# fpga.net
KiCad netlist of a schematic drawn in Altium Designer
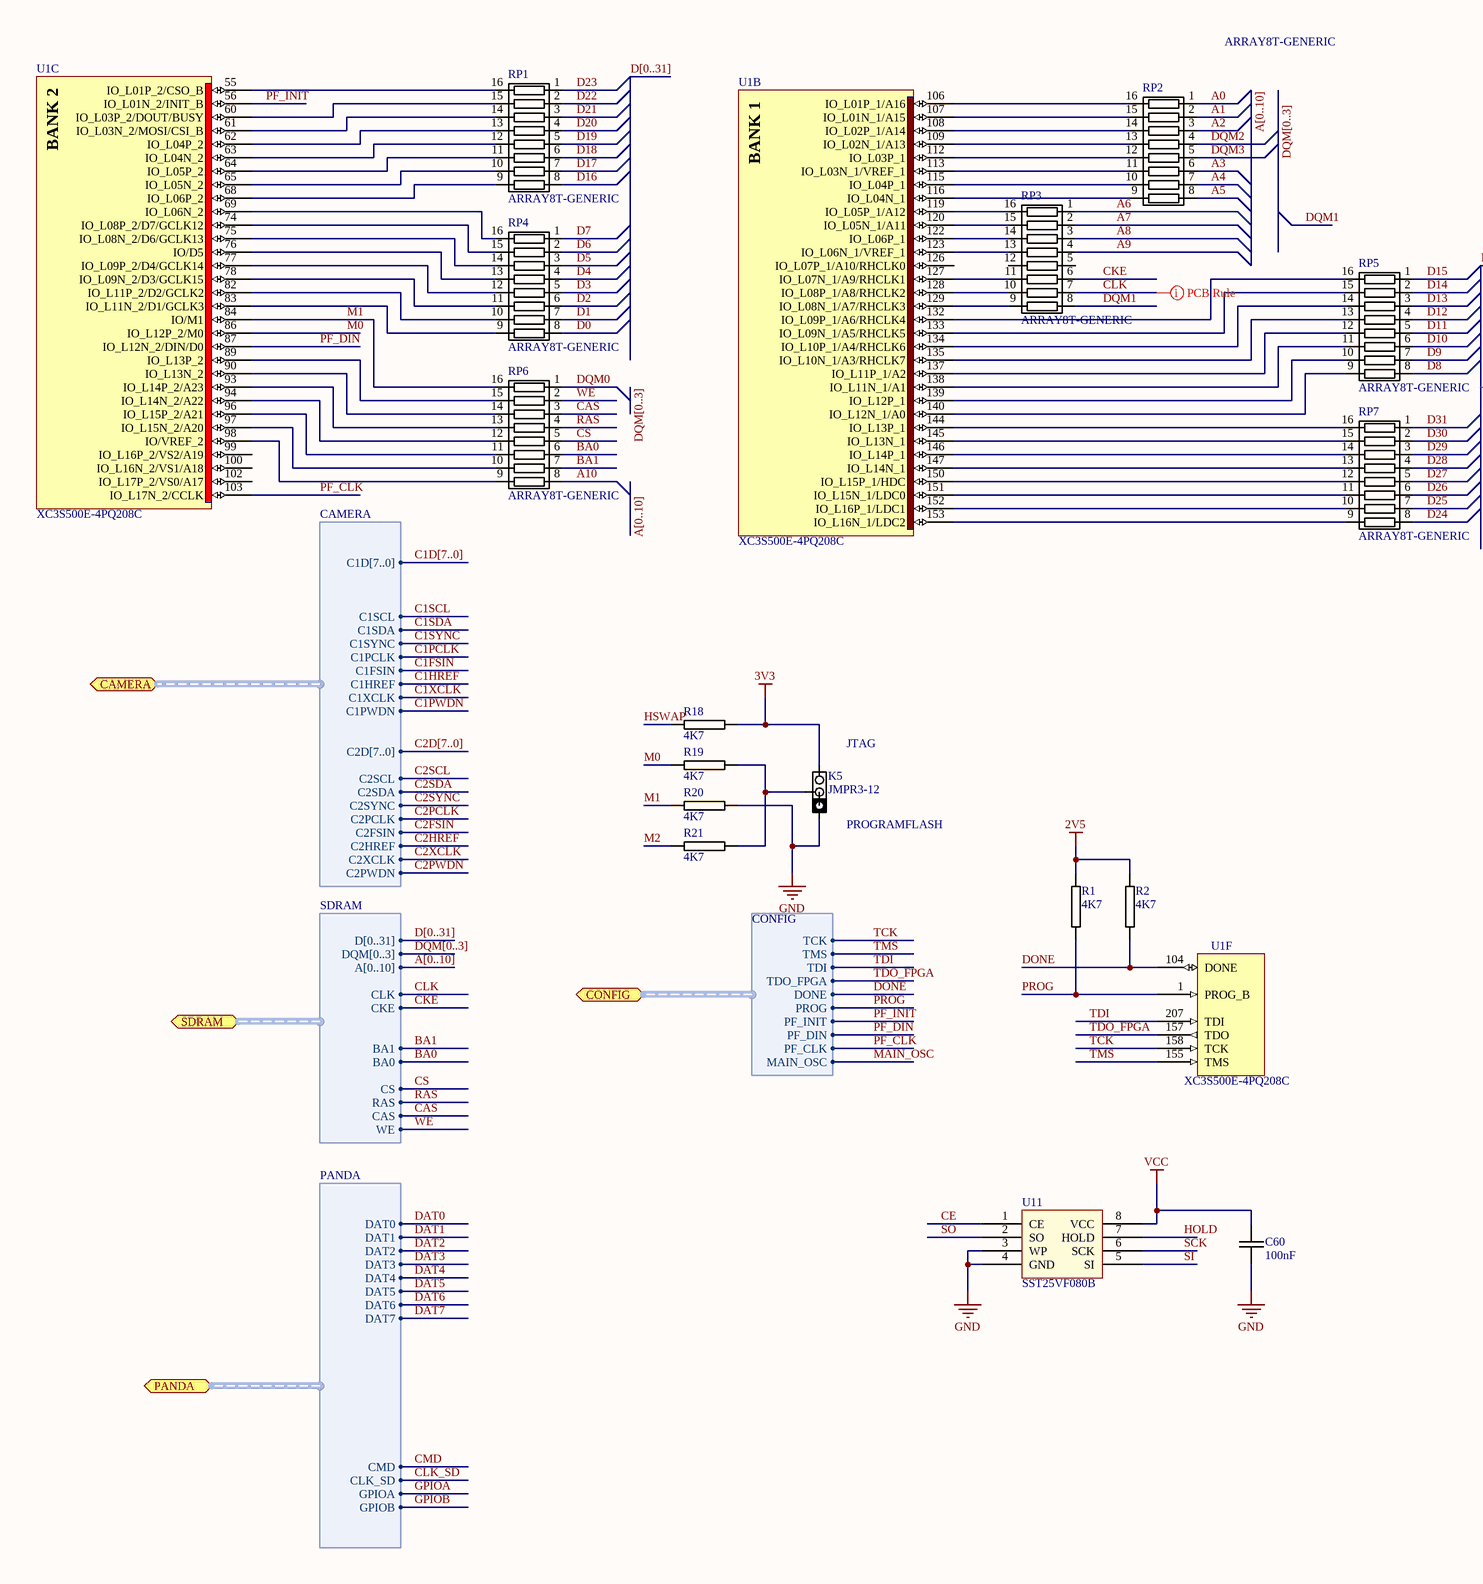
[diagram p0: fpga.SchDoc, left]
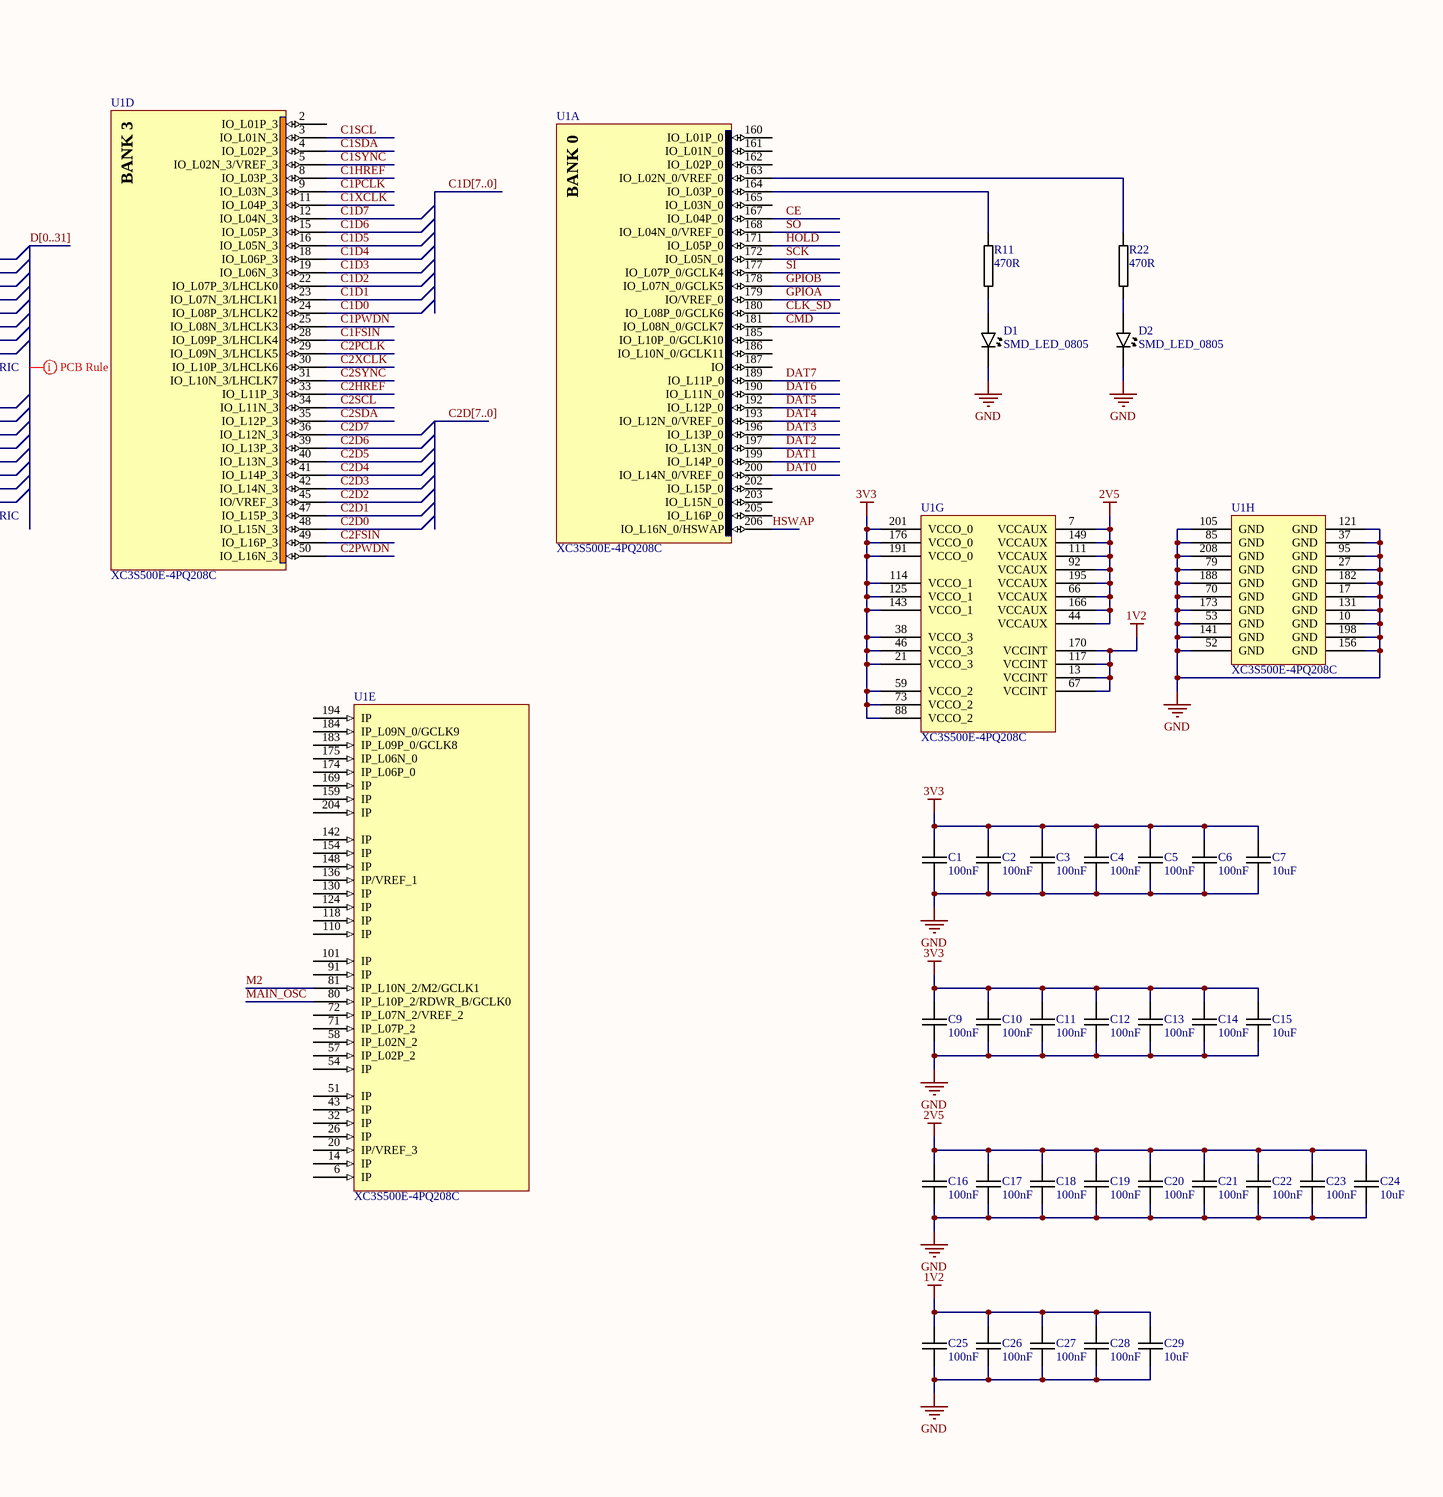
[diagram p1: fpga.SchDoc, right]

(export (version "E")
  (design (tool "Eeschema 10.0.6"))
  (components
    (comp (ref "C1")
      (value "100nF")
      (footprint "0603C-GENERIC")
      (description "GENERIC CAPACITOR NON POLARISED 0603")
      (fields (field (name "TOLERANCE") "±10%") (field (name "MANUFACTURER PART NUMBER") "C1608X7R1H103K"))
      (libsource (lib "vh_Altium Library") (part "0603C-100NF-50V-X7R-TDK"))
    )
    (comp (ref "C2")
      (value "100nF")
      (footprint "0603C-GENERIC")
      (description "GENERIC CAPACITOR NON POLARISED 0603")
      (fields (field (name "TOLERANCE") "±10%") (field (name "MANUFACTURER PART NUMBER") "C1608X7R1H103K"))
      (libsource (lib "vh_Altium Library") (part "0603C-100NF-50V-X7R-TDK"))
    )
    (comp (ref "C3")
      (value "100nF")
      (footprint "0603C-GENERIC")
      (description "GENERIC CAPACITOR NON POLARISED 0603")
      (fields (field (name "TOLERANCE") "±10%") (field (name "MANUFACTURER PART NUMBER") "C1608X7R1H103K"))
      (libsource (lib "vh_Altium Library") (part "0603C-100NF-50V-X7R-TDK"))
    )
    (comp (ref "C4")
      (value "100nF")
      (footprint "0603C-GENERIC")
      (description "GENERIC CAPACITOR NON POLARISED 0603")
      (fields (field (name "TOLERANCE") "±10%") (field (name "MANUFACTURER PART NUMBER") "C1608X7R1H103K"))
      (libsource (lib "vh_Altium Library") (part "0603C-100NF-50V-X7R-TDK"))
    )
    (comp (ref "C5")
      (value "100nF")
      (footprint "0603C-GENERIC")
      (description "GENERIC CAPACITOR NON POLARISED 0603")
      (fields (field (name "TOLERANCE") "±10%") (field (name "MANUFACTURER PART NUMBER") "C1608X7R1H103K"))
      (libsource (lib "vh_Altium Library") (part "0603C-100NF-50V-X7R-TDK"))
    )
    (comp (ref "C6")
      (value "100nF")
      (footprint "0603C-GENERIC")
      (description "GENERIC CAPACITOR NON POLARISED 0603")
      (fields (field (name "TOLERANCE") "±10%") (field (name "MANUFACTURER PART NUMBER") "C1608X7R1H103K"))
      (libsource (lib "vh_Altium Library") (part "0603C-100NF-50V-X7R-TDK"))
    )
    (comp (ref "C7")
      (value "10uF")
      (footprint "0805C-GENERIC")
      (description "CAPACITOR 0805 CERAMIC")
      (fields
        (field (name "MANUFACTURER PART NUMBER") "C2012X5R1C106M")
        (field (name "MANUFACTURER") "TDK Corporation")
      )
      (libsource (lib "vh_Altium Library") (part "0805C-10UF-16V-X5R-TDK"))
    )
    (comp (ref "C9")
      (value "100nF")
      (footprint "0603C-GENERIC")
      (description "GENERIC CAPACITOR NON POLARISED 0603")
      (fields (field (name "TOLERANCE") "±10%") (field (name "MANUFACTURER PART NUMBER") "C1608X7R1H103K"))
      (libsource (lib "vh_Altium Library") (part "0603C-100NF-50V-X7R-TDK"))
    )
    (comp (ref "C10")
      (value "100nF")
      (footprint "0603C-GENERIC")
      (description "GENERIC CAPACITOR NON POLARISED 0603")
      (fields (field (name "TOLERANCE") "±10%") (field (name "MANUFACTURER PART NUMBER") "C1608X7R1H103K"))
      (libsource (lib "vh_Altium Library") (part "0603C-100NF-50V-X7R-TDK"))
    )
    (comp (ref "C11")
      (value "100nF")
      (footprint "0603C-GENERIC")
      (description "GENERIC CAPACITOR NON POLARISED 0603")
      (fields (field (name "TOLERANCE") "±10%") (field (name "MANUFACTURER PART NUMBER") "C1608X7R1H103K"))
      (libsource (lib "vh_Altium Library") (part "0603C-100NF-50V-X7R-TDK"))
    )
    (comp (ref "C12")
      (value "100nF")
      (footprint "0603C-GENERIC")
      (description "GENERIC CAPACITOR NON POLARISED 0603")
      (fields (field (name "TOLERANCE") "±10%") (field (name "MANUFACTURER PART NUMBER") "C1608X7R1H103K"))
      (libsource (lib "vh_Altium Library") (part "0603C-100NF-50V-X7R-TDK"))
    )
    (comp (ref "C13")
      (value "100nF")
      (footprint "0603C-GENERIC")
      (description "GENERIC CAPACITOR NON POLARISED 0603")
      (fields (field (name "TOLERANCE") "±10%") (field (name "MANUFACTURER PART NUMBER") "C1608X7R1H103K"))
      (libsource (lib "vh_Altium Library") (part "0603C-100NF-50V-X7R-TDK"))
    )
    (comp (ref "C14")
      (value "100nF")
      (footprint "0603C-GENERIC")
      (description "GENERIC CAPACITOR NON POLARISED 0603")
      (fields (field (name "TOLERANCE") "±10%") (field (name "MANUFACTURER PART NUMBER") "C1608X7R1H103K"))
      (libsource (lib "vh_Altium Library") (part "0603C-100NF-50V-X7R-TDK"))
    )
    (comp (ref "C15")
      (value "10uF")
      (footprint "0805C-GENERIC")
      (description "CAPACITOR 0805 CERAMIC")
      (fields
        (field (name "MANUFACTURER PART NUMBER") "C2012X5R1C106M")
        (field (name "MANUFACTURER") "TDK Corporation")
      )
      (libsource (lib "vh_Altium Library") (part "0805C-10UF-16V-X5R-TDK"))
    )
    (comp (ref "C16")
      (value "100nF")
      (footprint "0603C-GENERIC")
      (description "GENERIC CAPACITOR NON POLARISED 0603")
      (fields (field (name "TOLERANCE") "±10%") (field (name "MANUFACTURER PART NUMBER") "C1608X7R1H103K"))
      (libsource (lib "vh_Altium Library") (part "0603C-100NF-50V-X7R-TDK"))
    )
    (comp (ref "C17")
      (value "100nF")
      (footprint "0603C-GENERIC")
      (description "GENERIC CAPACITOR NON POLARISED 0603")
      (fields (field (name "TOLERANCE") "±10%") (field (name "MANUFACTURER PART NUMBER") "C1608X7R1H103K"))
      (libsource (lib "vh_Altium Library") (part "0603C-100NF-50V-X7R-TDK"))
    )
    (comp (ref "C18")
      (value "100nF")
      (footprint "0603C-GENERIC")
      (description "GENERIC CAPACITOR NON POLARISED 0603")
      (fields (field (name "TOLERANCE") "±10%") (field (name "MANUFACTURER PART NUMBER") "C1608X7R1H103K"))
      (libsource (lib "vh_Altium Library") (part "0603C-100NF-50V-X7R-TDK"))
    )
    (comp (ref "C19")
      (value "100nF")
      (footprint "0603C-GENERIC")
      (description "GENERIC CAPACITOR NON POLARISED 0603")
      (fields (field (name "TOLERANCE") "±10%") (field (name "MANUFACTURER PART NUMBER") "C1608X7R1H103K"))
      (libsource (lib "vh_Altium Library") (part "0603C-100NF-50V-X7R-TDK"))
    )
    (comp (ref "C20")
      (value "100nF")
      (footprint "0603C-GENERIC")
      (description "GENERIC CAPACITOR NON POLARISED 0603")
      (fields (field (name "TOLERANCE") "±10%") (field (name "MANUFACTURER PART NUMBER") "C1608X7R1H103K"))
      (libsource (lib "vh_Altium Library") (part "0603C-100NF-50V-X7R-TDK"))
    )
    (comp (ref "C21")
      (value "100nF")
      (footprint "0603C-GENERIC")
      (description "GENERIC CAPACITOR NON POLARISED 0603")
      (fields (field (name "TOLERANCE") "±10%") (field (name "MANUFACTURER PART NUMBER") "C1608X7R1H103K"))
      (libsource (lib "vh_Altium Library") (part "0603C-100NF-50V-X7R-TDK"))
    )
    (comp (ref "C22")
      (value "100nF")
      (footprint "0603C-GENERIC")
      (description "GENERIC CAPACITOR NON POLARISED 0603")
      (fields (field (name "TOLERANCE") "±10%") (field (name "MANUFACTURER PART NUMBER") "C1608X7R1H103K"))
      (libsource (lib "vh_Altium Library") (part "0603C-100NF-50V-X7R-TDK"))
    )
    (comp (ref "C23")
      (value "100nF")
      (footprint "0603C-GENERIC")
      (description "GENERIC CAPACITOR NON POLARISED 0603")
      (fields (field (name "TOLERANCE") "±10%") (field (name "MANUFACTURER PART NUMBER") "C1608X7R1H103K"))
      (libsource (lib "vh_Altium Library") (part "0603C-100NF-50V-X7R-TDK"))
    )
    (comp (ref "C24")
      (value "10uF")
      (footprint "0805C-GENERIC")
      (description "CAPACITOR 0805 CERAMIC")
      (fields
        (field (name "MANUFACTURER PART NUMBER") "C2012X5R1C106M")
        (field (name "MANUFACTURER") "TDK Corporation")
      )
      (libsource (lib "vh_Altium Library") (part "0805C-10UF-16V-X5R-TDK"))
    )
    (comp (ref "C25")
      (value "100nF")
      (footprint "0603C-GENERIC")
      (description "GENERIC CAPACITOR NON POLARISED 0603")
      (fields (field (name "TOLERANCE") "±10%") (field (name "MANUFACTURER PART NUMBER") "C1608X7R1H103K"))
      (libsource (lib "vh_Altium Library") (part "0603C-100NF-50V-X7R-TDK"))
    )
    (comp (ref "C26")
      (value "100nF")
      (footprint "0603C-GENERIC")
      (description "GENERIC CAPACITOR NON POLARISED 0603")
      (fields (field (name "TOLERANCE") "±10%") (field (name "MANUFACTURER PART NUMBER") "C1608X7R1H103K"))
      (libsource (lib "vh_Altium Library") (part "0603C-100NF-50V-X7R-TDK"))
    )
    (comp (ref "C27")
      (value "100nF")
      (footprint "0603C-GENERIC")
      (description "GENERIC CAPACITOR NON POLARISED 0603")
      (fields (field (name "TOLERANCE") "±10%") (field (name "MANUFACTURER PART NUMBER") "C1608X7R1H103K"))
      (libsource (lib "vh_Altium Library") (part "0603C-100NF-50V-X7R-TDK"))
    )
    (comp (ref "C28")
      (value "100nF")
      (footprint "0603C-GENERIC")
      (description "GENERIC CAPACITOR NON POLARISED 0603")
      (fields (field (name "TOLERANCE") "±10%") (field (name "MANUFACTURER PART NUMBER") "C1608X7R1H103K"))
      (libsource (lib "vh_Altium Library") (part "0603C-100NF-50V-X7R-TDK"))
    )
    (comp (ref "C29")
      (value "10uF")
      (footprint "0805C-GENERIC")
      (description "CAPACITOR 0805 CERAMIC")
      (fields
        (field (name "MANUFACTURER PART NUMBER") "C2012X5R1C106M")
        (field (name "MANUFACTURER") "TDK Corporation")
      )
      (libsource (lib "vh_Altium Library") (part "0805C-10UF-16V-X5R-TDK"))
    )
    (comp (ref "C60")
      (value "100nF")
      (footprint "0603C-GENERIC")
      (description "GENERIC CAPACITOR NON POLARISED 0603")
      (fields (field (name "TOLERANCE") "±10%") (field (name "MANUFACTURER PART NUMBER") "C1608X7R1H103K"))
      (libsource (lib "vh_Altium Library") (part "0603C-100NF-50V-X7R-TDK"))
    )
    (comp (ref "D1")
      (value "SMD_LED_0805")
      (footprint "CD2012-0805")
      (libsource (lib "camera_board") (part "SMD_LED_0805"))
    )
    (comp (ref "D2")
      (value "SMD_LED_0805")
      (footprint "CD2012-0805")
      (libsource (lib "camera_board") (part "SMD_LED_0805"))
    )
    (comp (ref "K5")
      (value "JMPR3-12")
      (footprint "JMPR3-CLOSED-12")
      (description "CONN HEADER .100 SINGL STR 36POS")
      (fields (field (name "MANUFACTURER") "Sullins Connector Solutions"))
      (libsource (lib "vh_Altium Library") (part "JMPR3-12"))
    )
    (comp (ref "R1")
      (value "4K7")
      (footprint "0603R-4K7")
      (description "GENERIC RESISTOR 0603")
      (fields
        (field (name "MANUFACTURER") "Stackpole Electronics Inc")
        (field (name "MANUFACTURER PART NUMBER") "RMCF 1/16 4.7K 1% R")
      )
      (libsource (lib "vh_Altium Library") (part "0603R-4K7"))
    )
    (comp (ref "R2")
      (value "4K7")
      (footprint "0603R-4K7")
      (description "GENERIC RESISTOR 0603")
      (fields
        (field (name "MANUFACTURER") "Stackpole Electronics Inc")
        (field (name "MANUFACTURER PART NUMBER") "RMCF 1/16 4.7K 1% R")
      )
      (libsource (lib "vh_Altium Library") (part "0603R-4K7"))
    )
    (comp (ref "R11")
      (value "470R")
      (footprint "0603R-470")
      (description "GENERIC RESISTOR 0603")
      (fields (field (name "MANUFACTURER PART NUMBER") "RMCF 1/16 470 1% R") (field (name "TOLERANCE") "±1%"))
      (libsource (lib "vh_Altium Library") (part "0603R-470"))
    )
    (comp (ref "R18")
      (value "4K7")
      (footprint "0603R-4K7")
      (description "GENERIC RESISTOR 0603")
      (fields
        (field (name "MANUFACTURER") "Stackpole Electronics Inc")
        (field (name "MANUFACTURER PART NUMBER") "RMCF 1/16 4.7K 1% R")
      )
      (libsource (lib "vh_Altium Library") (part "0603R-4K7"))
    )
    (comp (ref "R19")
      (value "4K7")
      (footprint "0603R-4K7")
      (description "GENERIC RESISTOR 0603")
      (fields
        (field (name "MANUFACTURER") "Stackpole Electronics Inc")
        (field (name "MANUFACTURER PART NUMBER") "RMCF 1/16 4.7K 1% R")
      )
      (libsource (lib "vh_Altium Library") (part "0603R-4K7"))
    )
    (comp (ref "R20")
      (value "4K7")
      (footprint "0603R-4K7")
      (description "GENERIC RESISTOR 0603")
      (fields
        (field (name "MANUFACTURER") "Stackpole Electronics Inc")
        (field (name "MANUFACTURER PART NUMBER") "RMCF 1/16 4.7K 1% R")
      )
      (libsource (lib "vh_Altium Library") (part "0603R-4K7"))
    )
    (comp (ref "R21")
      (value "4K7")
      (footprint "0603R-4K7")
      (description "GENERIC RESISTOR 0603")
      (fields
        (field (name "MANUFACTURER") "Stackpole Electronics Inc")
        (field (name "MANUFACTURER PART NUMBER") "RMCF 1/16 4.7K 1% R")
      )
      (libsource (lib "vh_Altium Library") (part "0603R-4K7"))
    )
    (comp (ref "R22")
      (value "470R")
      (footprint "0603R-470")
      (description "GENERIC RESISTOR 0603")
      (fields (field (name "MANUFACTURER PART NUMBER") "RMCF 1/16 470 1% R") (field (name "TOLERANCE") "±1%"))
      (libsource (lib "vh_Altium Library") (part "0603R-470"))
    )
    (comp (ref "RP1")
      (value "ARRAY8T-GENERIC")
      (footprint "1206-ARRAY-8-GENERIC")
      (description "GENERIC RESISTOR ARRAY 8X INDEPENDENT")
      (libsource (lib "vh_Altium Library") (part "ARRAY8T-GENERIC"))
    )
    (comp (ref "RP2")
      (value "ARRAY8T-GENERIC")
      (footprint "1206-ARRAY-8-GENERIC")
      (description "GENERIC RESISTOR ARRAY 8X INDEPENDENT")
      (libsource (lib "vh_Altium Library") (part "ARRAY8T-GENERIC"))
    )
    (comp (ref "RP3")
      (value "ARRAY8T-GENERIC")
      (footprint "1206-ARRAY-8-GENERIC")
      (description "GENERIC RESISTOR ARRAY 8X INDEPENDENT")
      (libsource (lib "vh_Altium Library") (part "ARRAY8T-GENERIC"))
    )
    (comp (ref "RP4")
      (value "ARRAY8T-GENERIC")
      (footprint "1206-ARRAY-8-GENERIC")
      (description "GENERIC RESISTOR ARRAY 8X INDEPENDENT")
      (libsource (lib "vh_Altium Library") (part "ARRAY8T-GENERIC"))
    )
    (comp (ref "RP5")
      (value "ARRAY8T-GENERIC")
      (footprint "1206-ARRAY-8-GENERIC")
      (description "GENERIC RESISTOR ARRAY 8X INDEPENDENT")
      (libsource (lib "vh_Altium Library") (part "ARRAY8T-GENERIC"))
    )
    (comp (ref "RP6")
      (value "ARRAY8T-GENERIC")
      (footprint "1206-ARRAY-8-GENERIC")
      (description "GENERIC RESISTOR ARRAY 8X INDEPENDENT")
      (libsource (lib "vh_Altium Library") (part "ARRAY8T-GENERIC"))
    )
    (comp (ref "RP7")
      (value "ARRAY8T-GENERIC")
      (footprint "1206-ARRAY-8-GENERIC")
      (description "GENERIC RESISTOR ARRAY 8X INDEPENDENT")
      (libsource (lib "vh_Altium Library") (part "ARRAY8T-GENERIC"))
    )
    (comp (ref "U1")
      (value "XC3S500E-4PQ208C")
      (footprint "PQ208_N")
      (description "Spartan-3E 1.2V FPGA, 158 User I/Os, 208-Pin PQFP, Standard Performance, Commercial Grade")
      (fields (field (name "PUBLISHER") "Altium Limited"))
      (libsource (lib "Xilinx Spartan-3E") (part "XC3S500E-4PQ208C"))
    )
    (comp (ref "U11")
      (value "SST25VF080B")
      (footprint "SOIC127P600-8BM")
      (libsource (lib "camera_board") (part "SST25VF080B"))
    )
  )
  (nets
    (net (code "5") (name "/A0") (class "Default") (node (ref "RP2") (pin "1") (pintype "passive")))
    (net (code "6") (name "/A1") (class "Default") (node (ref "RP2") (pin "2") (pintype "passive")))
    (net (code "7") (name "/A2") (class "Default") (node (ref "RP2") (pin "3") (pintype "passive")))
    (net (code "8") (name "/A3") (class "Default") (node (ref "RP2") (pin "6") (pintype "passive")))
    (net (code "9") (name "/A4") (class "Default") (node (ref "RP2") (pin "7") (pintype "passive")))
    (net (code "10") (name "/A5") (class "Default") (node (ref "RP2") (pin "8") (pintype "passive")))
    (net (code "11") (name "/A6") (class "Default") (node (ref "RP3") (pin "1") (pintype "passive")))
    (net (code "12") (name "/A7") (class "Default") (node (ref "RP3") (pin "2") (pintype "passive")))
    (net (code "13") (name "/A8") (class "Default") (node (ref "RP3") (pin "3") (pintype "passive")))
    (net (code "14") (name "/A9") (class "Default") (node (ref "RP3") (pin "4") (pintype "passive")))
    (net (code "15") (name "/A10") (class "Default") (node (ref "RP6") (pin "8") (pintype "passive")))
    (net (code "17") (name "/BA0") (class "Default") (node (ref "RP6") (pin "6") (pintype "passive")))
    (net (code "18") (name "/BA1") (class "Default") (node (ref "RP6") (pin "7") (pintype "passive")))
    (net (code "19") (name "/C1D0") (class "Default")
      (node (ref "U1") (pin "24") (pinfunction "IO_L08P_3/LHCLK2_24") (pintype "bidirectional"))
    )
    (net (code "20") (name "/C1D1") (class "Default")
      (node (ref "U1") (pin "23") (pinfunction "IO_L07N_3/LHCLK1_23") (pintype "bidirectional"))
    )
    (net (code "21") (name "/C1D2") (class "Default")
      (node (ref "U1") (pin "22") (pinfunction "IO_L07P_3/LHCLK0_22") (pintype "bidirectional"))
    )
    (net (code "22") (name "/C1D3") (class "Default")
      (node (ref "U1") (pin "19") (pinfunction "IO_L06N_3_19") (pintype "bidirectional"))
    )
    (net (code "23") (name "/C1D4") (class "Default")
      (node (ref "U1") (pin "18") (pinfunction "IO_L06P_3_18") (pintype "bidirectional"))
    )
    (net (code "24") (name "/C1D5") (class "Default")
      (node (ref "U1") (pin "16") (pinfunction "IO_L05N_3_16") (pintype "bidirectional"))
    )
    (net (code "25") (name "/C1D6") (class "Default")
      (node (ref "U1") (pin "15") (pinfunction "IO_L05P_3_15") (pintype "bidirectional"))
    )
    (net (code "26") (name "/C1D7") (class "Default")
      (node (ref "U1") (pin "12") (pinfunction "IO_L04N_3_12") (pintype "bidirectional"))
    )
    (net (code "28") (name "/C1FSIN") (class "Default")
      (node (ref "U1") (pin "28") (pinfunction "IO_L09P_3/LHCLK4_28") (pintype "bidirectional"))
    )
    (net (code "29") (name "/C1HREF") (class "Default")
      (node (ref "U1") (pin "8") (pinfunction "IO_L03P_3_8") (pintype "bidirectional"))
    )
    (net (code "30") (name "/C1PCLK") (class "Default")
      (node (ref "U1") (pin "9") (pinfunction "IO_L03N_3_9") (pintype "bidirectional"))
    )
    (net (code "31") (name "/C1PWDN") (class "Default")
      (node (ref "U1") (pin "25") (pinfunction "IO_L08N_3/LHCLK3_25") (pintype "bidirectional"))
    )
    (net (code "32") (name "/C1SCL") (class "Default")
      (node (ref "U1") (pin "3") (pinfunction "IO_L01N_3_3") (pintype "bidirectional"))
    )
    (net (code "33") (name "/C1SDA") (class "Default")
      (node (ref "U1") (pin "4") (pinfunction "IO_L02P_3_4") (pintype "bidirectional"))
    )
    (net (code "34") (name "/C1SYNC") (class "Default")
      (node (ref "U1") (pin "5") (pinfunction "IO_L02N_3/VREF_3_5") (pintype "bidirectional"))
    )
    (net (code "35") (name "/C1XCLK") (class "Default")
      (node (ref "U1") (pin "11") (pinfunction "IO_L04P_3_11") (pintype "bidirectional"))
    )
    (net (code "36") (name "/C2D0") (class "Default")
      (node (ref "U1") (pin "48") (pinfunction "IO_L15N_3_48") (pintype "bidirectional"))
    )
    (net (code "37") (name "/C2D1") (class "Default")
      (node (ref "U1") (pin "47") (pinfunction "IO_L15P_3_47") (pintype "bidirectional"))
    )
    (net (code "38") (name "/C2D2") (class "Default")
      (node (ref "U1") (pin "45") (pinfunction "IO/VREF_3_45") (pintype "bidirectional"))
    )
    (net (code "39") (name "/C2D3") (class "Default")
      (node (ref "U1") (pin "42") (pinfunction "IO_L14N_3_42") (pintype "bidirectional"))
    )
    (net (code "40") (name "/C2D4") (class "Default")
      (node (ref "U1") (pin "41") (pinfunction "IO_L14P_3_41") (pintype "bidirectional"))
    )
    (net (code "41") (name "/C2D5") (class "Default")
      (node (ref "U1") (pin "40") (pinfunction "IO_L13N_3_40") (pintype "bidirectional"))
    )
    (net (code "42") (name "/C2D6") (class "Default")
      (node (ref "U1") (pin "39") (pinfunction "IO_L13P_3_39") (pintype "bidirectional"))
    )
    (net (code "43") (name "/C2D7") (class "Default")
      (node (ref "U1") (pin "36") (pinfunction "IO_L12N_3_36") (pintype "bidirectional"))
    )
    (net (code "45") (name "/C2FSIN") (class "Default")
      (node (ref "U1") (pin "49") (pinfunction "IO_L16P_3_49") (pintype "bidirectional"))
    )
    (net (code "46") (name "/C2HREF") (class "Default")
      (node (ref "U1") (pin "33") (pinfunction "IO_L11P_3_33") (pintype "bidirectional"))
    )
    (net (code "47") (name "/C2PCLK") (class "Default")
      (node (ref "U1") (pin "29") (pinfunction "IO_L09N_3/LHCLK5_29") (pintype "bidirectional"))
    )
    (net (code "48") (name "/C2PWDN") (class "Default")
      (node (ref "U1") (pin "50") (pinfunction "IO_L16N_3_50") (pintype "bidirectional"))
    )
    (net (code "49") (name "/C2SCL") (class "Default")
      (node (ref "U1") (pin "34") (pinfunction "IO_L11N_3_34") (pintype "bidirectional"))
    )
    (net (code "50") (name "/C2SDA") (class "Default")
      (node (ref "U1") (pin "35") (pinfunction "IO_L12P_3_35") (pintype "bidirectional"))
    )
    (net (code "51") (name "/C2SYNC") (class "Default")
      (node (ref "U1") (pin "31") (pinfunction "IO_L10N_3/LHCLK7_31") (pintype "bidirectional"))
    )
    (net (code "52") (name "/C2XCLK") (class "Default")
      (node (ref "U1") (pin "30") (pinfunction "IO_L10P_3/LHCLK6_30") (pintype "bidirectional"))
    )
    (net (code "54") (name "/CAS") (class "Default") (node (ref "RP6") (pin "3") (pintype "passive")))
    (net (code "55") (name "/CE") (class "Default")
      (node (ref "U1") (pin "167") (pinfunction "IO_L04P_0_167") (pintype "bidirectional"))
      (node (ref "U11") (pin "1") (pinfunction "CE_1") (pintype "passive"))
    )
    (net (code "56") (name "/CKE") (class "Default") (node (ref "RP3") (pin "6") (pintype "passive")))
    (net (code "57") (name "/CLK") (class "Default") (node (ref "RP3") (pin "7") (pintype "passive")))
    (net (code "58") (name "/CLK_SD") (class "Default")
      (node (ref "U1") (pin "180") (pinfunction "IO_L08P_0/GCLK6_180") (pintype "bidirectional"))
    )
    (net (code "59") (name "/CMD") (class "Default")
      (node (ref "U1") (pin "181") (pinfunction "IO_L08N_0/GCLK7_181") (pintype "bidirectional"))
    )
    (net (code "60") (name "/CS") (class "Default") (node (ref "RP6") (pin "5") (pintype "passive")))
    (net (code "61") (name "/D0") (class "Default") (node (ref "RP4") (pin "8") (pintype "passive")))
    (net (code "62") (name "/D1") (class "Default") (node (ref "RP4") (pin "7") (pintype "passive")))
    (net (code "63") (name "/D2") (class "Default") (node (ref "RP4") (pin "6") (pintype "passive")))
    (net (code "64") (name "/D3") (class "Default") (node (ref "RP4") (pin "5") (pintype "passive")))
    (net (code "65") (name "/D4") (class "Default") (node (ref "RP4") (pin "4") (pintype "passive")))
    (net (code "66") (name "/D5") (class "Default") (node (ref "RP4") (pin "3") (pintype "passive")))
    (net (code "67") (name "/D6") (class "Default") (node (ref "RP4") (pin "2") (pintype "passive")))
    (net (code "68") (name "/D7") (class "Default") (node (ref "RP4") (pin "1") (pintype "passive")))
    (net (code "69") (name "/D8") (class "Default") (node (ref "RP5") (pin "8") (pintype "passive")))
    (net (code "70") (name "/D9") (class "Default") (node (ref "RP5") (pin "7") (pintype "passive")))
    (net (code "71") (name "/D10") (class "Default") (node (ref "RP5") (pin "6") (pintype "passive")))
    (net (code "72") (name "/D11") (class "Default") (node (ref "RP5") (pin "5") (pintype "passive")))
    (net (code "73") (name "/D12") (class "Default") (node (ref "RP5") (pin "4") (pintype "passive")))
    (net (code "74") (name "/D13") (class "Default") (node (ref "RP5") (pin "3") (pintype "passive")))
    (net (code "75") (name "/D14") (class "Default") (node (ref "RP5") (pin "2") (pintype "passive")))
    (net (code "76") (name "/D15") (class "Default") (node (ref "RP5") (pin "1") (pintype "passive")))
    (net (code "77") (name "/D16") (class "Default") (node (ref "RP1") (pin "8") (pintype "passive")))
    (net (code "78") (name "/D17") (class "Default") (node (ref "RP1") (pin "7") (pintype "passive")))
    (net (code "79") (name "/D18") (class "Default") (node (ref "RP1") (pin "6") (pintype "passive")))
    (net (code "80") (name "/D19") (class "Default") (node (ref "RP1") (pin "5") (pintype "passive")))
    (net (code "81") (name "/D20") (class "Default") (node (ref "RP1") (pin "4") (pintype "passive")))
    (net (code "82") (name "/D21") (class "Default") (node (ref "RP1") (pin "3") (pintype "passive")))
    (net (code "83") (name "/D22") (class "Default") (node (ref "RP1") (pin "2") (pintype "passive")))
    (net (code "84") (name "/D23") (class "Default") (node (ref "RP1") (pin "1") (pintype "passive")))
    (net (code "85") (name "/D24") (class "Default") (node (ref "RP7") (pin "8") (pintype "passive")))
    (net (code "86") (name "/D25") (class "Default") (node (ref "RP7") (pin "7") (pintype "passive")))
    (net (code "87") (name "/D26") (class "Default") (node (ref "RP7") (pin "6") (pintype "passive")))
    (net (code "88") (name "/D27") (class "Default") (node (ref "RP7") (pin "5") (pintype "passive")))
    (net (code "89") (name "/D28") (class "Default") (node (ref "RP7") (pin "4") (pintype "passive")))
    (net (code "90") (name "/D29") (class "Default") (node (ref "RP7") (pin "3") (pintype "passive")))
    (net (code "91") (name "/D30") (class "Default") (node (ref "RP7") (pin "2") (pintype "passive")))
    (net (code "92") (name "/D31") (class "Default") (node (ref "RP7") (pin "1") (pintype "passive")))
    (net (code "93") (name "/DAT0") (class "Default")
      (node (ref "U1") (pin "200") (pinfunction "IO_L14N_0/VREF_0_200") (pintype "bidirectional"))
    )
    (net (code "94") (name "/DAT1") (class "Default")
      (node (ref "U1") (pin "199") (pinfunction "IO_L14P_0_199") (pintype "bidirectional"))
    )
    (net (code "95") (name "/DAT2") (class "Default")
      (node (ref "U1") (pin "197") (pinfunction "IO_L13N_0_197") (pintype "bidirectional"))
    )
    (net (code "96") (name "/DAT3") (class "Default")
      (node (ref "U1") (pin "196") (pinfunction "IO_L13P_0_196") (pintype "bidirectional"))
    )
    (net (code "97") (name "/DAT4") (class "Default")
      (node (ref "U1") (pin "193") (pinfunction "IO_L12N_0/VREF_0_193") (pintype "bidirectional"))
    )
    (net (code "98") (name "/DAT5") (class "Default")
      (node (ref "U1") (pin "192") (pinfunction "IO_L12P_0_192") (pintype "bidirectional"))
    )
    (net (code "99") (name "/DAT6") (class "Default")
      (node (ref "U1") (pin "190") (pinfunction "IO_L11N_0_190") (pintype "bidirectional"))
    )
    (net (code "100") (name "/DAT7") (class "Default")
      (node (ref "U1") (pin "189") (pinfunction "IO_L11P_0_189") (pintype "bidirectional"))
    )
    (net (code "101") (name "/DONE") (class "Default")
      (node (ref "R2") (pin "2") (pintype "passive"))
      (node (ref "U1") (pin "104") (pinfunction "DONE_104") (pintype "bidirectional"))
    )
    (net (code "102") (name "/DQM0") (class "Default") (node (ref "RP6") (pin "1") (pintype "passive")))
    (net (code "103") (name "/DQM1") (class "Default") (node (ref "RP3") (pin "8") (pintype "passive")))
    (net (code "104") (name "/DQM2") (class "Default") (node (ref "RP2") (pin "4") (pintype "passive")))
    (net (code "105") (name "/DQM3") (class "Default") (node (ref "RP2") (pin "5") (pintype "passive")))
    (net (code "108") (name "/GPIOA") (class "Default")
      (node (ref "U1") (pin "179") (pinfunction "IO/VREF_0_179") (pintype "bidirectional"))
    )
    (net (code "109") (name "/GPIOB") (class "Default")
      (node (ref "U1") (pin "178") (pinfunction "IO_L07N_0/GCLK5_178") (pintype "bidirectional"))
    )
    (net (code "110") (name "/HOLD") (class "Default")
      (node (ref "U1") (pin "171") (pinfunction "IO_L05P_0_171") (pintype "bidirectional"))
      (node (ref "U11") (pin "7") (pinfunction "HOLD_7") (pintype "passive"))
    )
    (net (code "111") (name "/HSWAP") (class "Default")
      (node (ref "R18") (pin "1") (pintype "passive"))
      (node (ref "U1") (pin "206") (pinfunction "IO_L16N_0/HSWAP_206") (pintype "bidirectional"))
    )
    (net (code "112") (name "/M0") (class "Default")
      (node (ref "R19") (pin "1") (pintype "passive"))
      (node (ref "U1") (pin "86") (pinfunction "IO_L12P_2/M0_86") (pintype "bidirectional"))
    )
    (net (code "113") (name "/M1") (class "Default")
      (node (ref "R20") (pin "1") (pintype "passive"))
      (node (ref "RP6") (pin "16") (pintype "passive"))
      (node (ref "U1") (pin "84") (pinfunction "IO/M1_84") (pintype "bidirectional"))
    )
    (net (code "114") (name "/M2") (class "Default")
      (node (ref "R21") (pin "1") (pintype "passive"))
      (node (ref "U1") (pin "81") (pinfunction "IP_L10N_2/M2/GCLK1_81") (pintype "input"))
    )
    (net (code "115") (name "/MAIN_OSC") (class "Default")
      (node (ref "U1") (pin "80") (pinfunction "IP_L10P_2/RDWR_B/GCLK0_80") (pintype "input"))
    )
    (net (code "116") (name "/PF_CLK") (class "Default")
      (node (ref "U1") (pin "103") (pinfunction "IO_L17N_2/CCLK_103") (pintype "bidirectional"))
    )
    (net (code "117") (name "/PF_DIN") (class "Default")
      (node (ref "U1") (pin "87") (pinfunction "IO_L12N_2/DIN/D0_87") (pintype "bidirectional"))
    )
    (net (code "118") (name "/PF_INIT") (class "Default")
      (node (ref "U1") (pin "56") (pinfunction "IO_L01N_2/INIT_B_56") (pintype "bidirectional"))
    )
    (net (code "119") (name "/PROG") (class "Default")
      (node (ref "R1") (pin "2") (pintype "passive"))
      (node (ref "U1") (pin "1") (pinfunction "PROG_B_1") (pintype "input"))
    )
    (net (code "120") (name "/RAS") (class "Default") (node (ref "RP6") (pin "4") (pintype "passive")))
    (net (code "121") (name "/SCK") (class "Default")
      (node (ref "U1") (pin "172") (pinfunction "IO_L05N_0_172") (pintype "bidirectional"))
      (node (ref "U11") (pin "6") (pinfunction "SCK_6") (pintype "passive"))
    )
    (net (code "123") (name "/SI") (class "Default")
      (node (ref "U1") (pin "177") (pinfunction "IO_L07P_0/GCLK4_177") (pintype "bidirectional"))
      (node (ref "U11") (pin "5") (pinfunction "SI_5") (pintype "passive"))
    )
    (net (code "124") (name "/SO") (class "Default")
      (node (ref "U1") (pin "168") (pinfunction "IO_L04N_0/VREF_0_168") (pintype "bidirectional"))
      (node (ref "U11") (pin "2") (pinfunction "SO_2") (pintype "passive"))
    )
    (net (code "125") (name "/TCK") (class "Default")
      (node (ref "U1") (pin "158") (pinfunction "TCK_158") (pintype "input"))
    )
    (net (code "126") (name "/TDI") (class "Default")
      (node (ref "U1") (pin "207") (pinfunction "TDI_207") (pintype "input"))
    )
    (net (code "127") (name "/TDO_FPGA") (class "Default")
      (node (ref "U1") (pin "157") (pinfunction "TDO_157") (pintype "output"))
    )
    (net (code "128") (name "/TMS") (class "Default")
      (node (ref "U1") (pin "155") (pinfunction "TMS_155") (pintype "input"))
    )
    (net (code "129") (name "/WE") (class "Default") (node (ref "RP6") (pin "2") (pintype "passive")))
    (net (code "134") (name "1V2") (class "Default")
      (node (ref "C25") (pin "1") (pintype "passive"))
      (node (ref "C26") (pin "1") (pintype "passive"))
      (node (ref "C27") (pin "1") (pintype "passive"))
      (node (ref "C28") (pin "1") (pintype "passive"))
      (node (ref "C29") (pin "1") (pintype "passive"))
      (node (ref "U1") (pin "117") (pinfunction "VCCINT_117") (pintype "power_in"))
      (node (ref "U1") (pin "13") (pinfunction "VCCINT_13") (pintype "power_in"))
      (node (ref "U1") (pin "170") (pinfunction "VCCINT_170") (pintype "power_in"))
      (node (ref "U1") (pin "67") (pinfunction "VCCINT_67") (pintype "power_in"))
    )
    (net (code "135") (name "2V5") (class "Default")
      (node (ref "C16") (pin "1") (pintype "passive"))
      (node (ref "C17") (pin "1") (pintype "passive"))
      (node (ref "C18") (pin "1") (pintype "passive"))
      (node (ref "C19") (pin "1") (pintype "passive"))
      (node (ref "C20") (pin "1") (pintype "passive"))
      (node (ref "C21") (pin "1") (pintype "passive"))
      (node (ref "C22") (pin "1") (pintype "passive"))
      (node (ref "C23") (pin "1") (pintype "passive"))
      (node (ref "C24") (pin "1") (pintype "passive"))
      (node (ref "R1") (pin "1") (pintype "passive"))
      (node (ref "R2") (pin "1") (pintype "passive"))
      (node (ref "U1") (pin "111") (pinfunction "VCCAUX_111") (pintype "power_in"))
      (node (ref "U1") (pin "149") (pinfunction "VCCAUX_149") (pintype "power_in"))
      (node (ref "U1") (pin "166") (pinfunction "VCCAUX_166") (pintype "power_in"))
      (node (ref "U1") (pin "195") (pinfunction "VCCAUX_195") (pintype "power_in"))
      (node (ref "U1") (pin "44") (pinfunction "VCCAUX_44") (pintype "power_in"))
      (node (ref "U1") (pin "66") (pinfunction "VCCAUX_66") (pintype "power_in"))
      (node (ref "U1") (pin "7") (pinfunction "VCCAUX_7") (pintype "power_in"))
      (node (ref "U1") (pin "92") (pinfunction "VCCAUX_92") (pintype "power_in"))
    )
    (net (code "136") (name "3V3") (class "Default")
      (node (ref "C1") (pin "1") (pintype "passive"))
      (node (ref "C10") (pin "1") (pintype "passive"))
      (node (ref "C11") (pin "1") (pintype "passive"))
      (node (ref "C12") (pin "1") (pintype "passive"))
      (node (ref "C13") (pin "1") (pintype "passive"))
      (node (ref "C14") (pin "1") (pintype "passive"))
      (node (ref "C15") (pin "1") (pintype "passive"))
      (node (ref "C2") (pin "1") (pintype "passive"))
      (node (ref "C3") (pin "1") (pintype "passive"))
      (node (ref "C4") (pin "1") (pintype "passive"))
      (node (ref "C5") (pin "1") (pintype "passive"))
      (node (ref "C6") (pin "1") (pintype "passive"))
      (node (ref "C7") (pin "1") (pintype "passive"))
      (node (ref "C9") (pin "1") (pintype "passive"))
      (node (ref "K5") (pin "3") (pintype "passive"))
      (node (ref "R18") (pin "2") (pintype "passive"))
      (node (ref "U1") (pin "114") (pinfunction "VCCO_1_114") (pintype "power_in"))
      (node (ref "U1") (pin "125") (pinfunction "VCCO_1_125") (pintype "power_in"))
      (node (ref "U1") (pin "143") (pinfunction "VCCO_1_143") (pintype "power_in"))
      (node (ref "U1") (pin "176") (pinfunction "VCCO_0_176") (pintype "power_in"))
      (node (ref "U1") (pin "191") (pinfunction "VCCO_0_191") (pintype "power_in"))
      (node (ref "U1") (pin "201") (pinfunction "VCCO_0_201") (pintype "power_in"))
      (node (ref "U1") (pin "21") (pinfunction "VCCO_3_21") (pintype "power_in"))
      (node (ref "U1") (pin "38") (pinfunction "VCCO_3_38") (pintype "power_in"))
      (node (ref "U1") (pin "46") (pinfunction "VCCO_3_46") (pintype "power_in"))
      (node (ref "U1") (pin "59") (pinfunction "VCCO_2_59") (pintype "power_in"))
      (node (ref "U1") (pin "73") (pinfunction "VCCO_2_73") (pintype "power_in"))
      (node (ref "U1") (pin "88") (pinfunction "VCCO_2_88") (pintype "power_in"))
    )
    (net (code "137") (name "GND") (class "Default")
      (node (ref "C1") (pin "2") (pintype "passive"))
      (node (ref "C10") (pin "2") (pintype "passive"))
      (node (ref "C11") (pin "2") (pintype "passive"))
      (node (ref "C12") (pin "2") (pintype "passive"))
      (node (ref "C13") (pin "2") (pintype "passive"))
      (node (ref "C14") (pin "2") (pintype "passive"))
      (node (ref "C15") (pin "2") (pintype "passive"))
      (node (ref "C16") (pin "2") (pintype "passive"))
      (node (ref "C17") (pin "2") (pintype "passive"))
      (node (ref "C18") (pin "2") (pintype "passive"))
      (node (ref "C19") (pin "2") (pintype "passive"))
      (node (ref "C2") (pin "2") (pintype "passive"))
      (node (ref "C20") (pin "2") (pintype "passive"))
      (node (ref "C21") (pin "2") (pintype "passive"))
      (node (ref "C22") (pin "2") (pintype "passive"))
      (node (ref "C23") (pin "2") (pintype "passive"))
      (node (ref "C24") (pin "2") (pintype "passive"))
      (node (ref "C25") (pin "2") (pintype "passive"))
      (node (ref "C26") (pin "2") (pintype "passive"))
      (node (ref "C27") (pin "2") (pintype "passive"))
      (node (ref "C28") (pin "2") (pintype "passive"))
      (node (ref "C29") (pin "2") (pintype "passive"))
      (node (ref "C3") (pin "2") (pintype "passive"))
      (node (ref "C4") (pin "2") (pintype "passive"))
      (node (ref "C5") (pin "2") (pintype "passive"))
      (node (ref "C6") (pin "2") (pintype "passive"))
      (node (ref "C60") (pin "2") (pintype "passive"))
      (node (ref "C7") (pin "2") (pintype "passive"))
      (node (ref "C9") (pin "2") (pintype "passive"))
      (node (ref "D1") (pin "2") (pinfunction "K_2") (pintype "passive"))
      (node (ref "D2") (pin "2") (pinfunction "K_2") (pintype "passive"))
      (node (ref "K5") (pin "1") (pintype "passive"))
      (node (ref "R20") (pin "2") (pintype "passive"))
      (node (ref "U1") (pin "10") (pinfunction "GND_10") (pintype "power_in"))
      (node (ref "U1") (pin "105") (pinfunction "GND_105") (pintype "power_in"))
      (node (ref "U1") (pin "121") (pinfunction "GND_121") (pintype "power_in"))
      (node (ref "U1") (pin "131") (pinfunction "GND_131") (pintype "power_in"))
      (node (ref "U1") (pin "141") (pinfunction "GND_141") (pintype "power_in"))
      (node (ref "U1") (pin "156") (pinfunction "GND_156") (pintype "power_in"))
      (node (ref "U1") (pin "17") (pinfunction "GND_17") (pintype "power_in"))
      (node (ref "U1") (pin "173") (pinfunction "GND_173") (pintype "power_in"))
      (node (ref "U1") (pin "182") (pinfunction "GND_182") (pintype "power_in"))
      (node (ref "U1") (pin "188") (pinfunction "GND_188") (pintype "power_in"))
      (node (ref "U1") (pin "198") (pinfunction "GND_198") (pintype "power_in"))
      (node (ref "U1") (pin "208") (pinfunction "GND_208") (pintype "power_in"))
      (node (ref "U1") (pin "27") (pinfunction "GND_27") (pintype "power_in"))
      (node (ref "U1") (pin "37") (pinfunction "GND_37") (pintype "power_in"))
      (node (ref "U1") (pin "52") (pinfunction "GND_52") (pintype "power_in"))
      (node (ref "U1") (pin "53") (pinfunction "GND_53") (pintype "power_in"))
      (node (ref "U1") (pin "70") (pinfunction "GND_70") (pintype "power_in"))
      (node (ref "U1") (pin "79") (pinfunction "GND_79") (pintype "power_in"))
      (node (ref "U1") (pin "85") (pinfunction "GND_85") (pintype "power_in"))
      (node (ref "U1") (pin "95") (pinfunction "GND_95") (pintype "power_in"))
      (node (ref "U11") (pin "3") (pinfunction "WP_3") (pintype "passive"))
      (node (ref "U11") (pin "4") (pinfunction "GND_4") (pintype "passive"))
    )
    (net (code "138") (name "Net-(D1-A)") (class "Default")
      (node (ref "D1") (pin "1") (pinfunction "A_1") (pintype "passive"))
      (node (ref "R11") (pin "2") (pintype "passive"))
    )
    (net (code "139") (name "Net-(D2-A)") (class "Default")
      (node (ref "D2") (pin "1") (pinfunction "A_1") (pintype "passive"))
      (node (ref "R22") (pin "2") (pintype "passive"))
    )
    (net (code "140") (name "Net-(K5-Pad2)") (class "Default")
      (node (ref "K5") (pin "2") (pintype "passive"))
      (node (ref "R19") (pin "2") (pintype "passive"))
      (node (ref "R21") (pin "2") (pintype "passive"))
    )
    (net (code "141") (name "Net-(U1A-IO_L02N_0{slash}VREF_0)") (class "Default")
      (node (ref "R22") (pin "1") (pintype "passive"))
      (node (ref "U1") (pin "163") (pinfunction "IO_L02N_0/VREF_0_163") (pintype "bidirectional"))
    )
    (net (code "142") (name "Net-(U1A-IO_L03P_0)") (class "Default")
      (node (ref "R11") (pin "1") (pintype "passive"))
      (node (ref "U1") (pin "164") (pinfunction "IO_L03P_0_164") (pintype "bidirectional"))
    )
    (net (code "143") (name "Net-(U1B-IO_L01N_1{slash}A15)") (class "Default")
      (node (ref "RP2") (pin "15") (pintype "passive"))
      (node (ref "U1") (pin "107") (pinfunction "IO_L01N_1/A15_107") (pintype "bidirectional"))
    )
    (net (code "144") (name "Net-(U1B-IO_L01P_1{slash}A16)") (class "Default")
      (node (ref "RP2") (pin "16") (pintype "passive"))
      (node (ref "U1") (pin "106") (pinfunction "IO_L01P_1/A16_106") (pintype "bidirectional"))
    )
    (net (code "145") (name "Net-(U1B-IO_L02N_1{slash}A13)") (class "Default")
      (node (ref "RP2") (pin "13") (pintype "passive"))
      (node (ref "U1") (pin "109") (pinfunction "IO_L02N_1/A13_109") (pintype "bidirectional"))
    )
    (net (code "146") (name "Net-(U1B-IO_L02P_1{slash}A14)") (class "Default")
      (node (ref "RP2") (pin "14") (pintype "passive"))
      (node (ref "U1") (pin "108") (pinfunction "IO_L02P_1/A14_108") (pintype "bidirectional"))
    )
    (net (code "147") (name "Net-(U1B-IO_L03N_1{slash}VREF_1)") (class "Default")
      (node (ref "RP2") (pin "11") (pintype "passive"))
      (node (ref "U1") (pin "113") (pinfunction "IO_L03N_1/VREF_1_113") (pintype "bidirectional"))
    )
    (net (code "148") (name "Net-(U1B-IO_L03P_1)") (class "Default")
      (node (ref "RP2") (pin "12") (pintype "passive"))
      (node (ref "U1") (pin "112") (pinfunction "IO_L03P_1_112") (pintype "bidirectional"))
    )
    (net (code "149") (name "Net-(U1B-IO_L04N_1)") (class "Default")
      (node (ref "RP2") (pin "9") (pintype "passive"))
      (node (ref "U1") (pin "116") (pinfunction "IO_L04N_1_116") (pintype "bidirectional"))
    )
    (net (code "150") (name "Net-(U1B-IO_L04P_1)") (class "Default")
      (node (ref "RP2") (pin "10") (pintype "passive"))
      (node (ref "U1") (pin "115") (pinfunction "IO_L04P_1_115") (pintype "bidirectional"))
    )
    (net (code "151") (name "Net-(U1B-IO_L05N_1{slash}A11)") (class "Default")
      (node (ref "RP3") (pin "15") (pintype "passive"))
      (node (ref "U1") (pin "120") (pinfunction "IO_L05N_1/A11_120") (pintype "bidirectional"))
    )
    (net (code "152") (name "Net-(U1B-IO_L05P_1{slash}A12)") (class "Default")
      (node (ref "RP3") (pin "16") (pintype "passive"))
      (node (ref "U1") (pin "119") (pinfunction "IO_L05P_1/A12_119") (pintype "bidirectional"))
    )
    (net (code "153") (name "Net-(U1B-IO_L06N_1{slash}VREF_1)") (class "Default")
      (node (ref "RP3") (pin "13") (pintype "passive"))
      (node (ref "U1") (pin "123") (pinfunction "IO_L06N_1/VREF_1_123") (pintype "bidirectional"))
    )
    (net (code "154") (name "Net-(U1B-IO_L06P_1)") (class "Default")
      (node (ref "RP3") (pin "14") (pintype "passive"))
      (node (ref "U1") (pin "122") (pinfunction "IO_L06P_1_122") (pintype "bidirectional"))
    )
    (net (code "155") (name "Net-(U1B-IO_L07N_1{slash}A9{slash}RHCLK1)") (class "Default")
      (node (ref "RP3") (pin "11") (pintype "passive"))
      (node (ref "U1") (pin "127") (pinfunction "IO_L07N_1/A9/RHCLK1_127") (pintype "bidirectional"))
    )
    (net (code "156") (name "Net-(U1B-IO_L08N_1{slash}A7{slash}RHCLK3)") (class "Default")
      (node (ref "RP3") (pin "9") (pintype "passive"))
      (node (ref "U1") (pin "129") (pinfunction "IO_L08N_1/A7/RHCLK3_129") (pintype "bidirectional"))
    )
    (net (code "157") (name "Net-(U1B-IO_L08P_1{slash}A8{slash}RHCLK2)") (class "Default")
      (node (ref "RP3") (pin "10") (pintype "passive"))
      (node (ref "U1") (pin "128") (pinfunction "IO_L08P_1/A8/RHCLK2_128") (pintype "bidirectional"))
    )
    (net (code "158") (name "Net-(U1B-IO_L09N_1{slash}A5{slash}RHCLK5)") (class "Default")
      (node (ref "RP5") (pin "15") (pintype "passive"))
      (node (ref "U1") (pin "133") (pinfunction "IO_L09N_1/A5/RHCLK5_133") (pintype "bidirectional"))
    )
    (net (code "159") (name "Net-(U1B-IO_L09P_1{slash}A6{slash}RHCLK4)") (class "Default")
      (node (ref "RP5") (pin "16") (pintype "passive"))
      (node (ref "U1") (pin "132") (pinfunction "IO_L09P_1/A6/RHCLK4_132") (pintype "bidirectional"))
    )
    (net (code "160") (name "Net-(U1B-IO_L10N_1{slash}A3{slash}RHCLK7)") (class "Default")
      (node (ref "RP5") (pin "13") (pintype "passive"))
      (node (ref "U1") (pin "135") (pinfunction "IO_L10N_1/A3/RHCLK7_135") (pintype "bidirectional"))
    )
    (net (code "161") (name "Net-(U1B-IO_L10P_1{slash}A4{slash}RHCLK6)") (class "Default")
      (node (ref "RP5") (pin "14") (pintype "passive"))
      (node (ref "U1") (pin "134") (pinfunction "IO_L10P_1/A4/RHCLK6_134") (pintype "bidirectional"))
    )
    (net (code "162") (name "Net-(U1B-IO_L11N_1{slash}A1)") (class "Default")
      (node (ref "RP5") (pin "11") (pintype "passive"))
      (node (ref "U1") (pin "138") (pinfunction "IO_L11N_1/A1_138") (pintype "bidirectional"))
    )
    (net (code "163") (name "Net-(U1B-IO_L11P_1{slash}A2)") (class "Default")
      (node (ref "RP5") (pin "12") (pintype "passive"))
      (node (ref "U1") (pin "137") (pinfunction "IO_L11P_1/A2_137") (pintype "bidirectional"))
    )
    (net (code "164") (name "Net-(U1B-IO_L12N_1{slash}A0)") (class "Default")
      (node (ref "RP5") (pin "9") (pintype "passive"))
      (node (ref "U1") (pin "140") (pinfunction "IO_L12N_1/A0_140") (pintype "bidirectional"))
    )
    (net (code "165") (name "Net-(U1B-IO_L12P_1)") (class "Default")
      (node (ref "RP5") (pin "10") (pintype "passive"))
      (node (ref "U1") (pin "139") (pinfunction "IO_L12P_1_139") (pintype "bidirectional"))
    )
    (net (code "166") (name "Net-(U1B-IO_L13N_1)") (class "Default")
      (node (ref "RP7") (pin "15") (pintype "passive"))
      (node (ref "U1") (pin "145") (pinfunction "IO_L13N_1_145") (pintype "bidirectional"))
    )
    (net (code "167") (name "Net-(U1B-IO_L13P_1)") (class "Default")
      (node (ref "RP7") (pin "16") (pintype "passive"))
      (node (ref "U1") (pin "144") (pinfunction "IO_L13P_1_144") (pintype "bidirectional"))
    )
    (net (code "168") (name "Net-(U1B-IO_L14N_1)") (class "Default")
      (node (ref "RP7") (pin "13") (pintype "passive"))
      (node (ref "U1") (pin "147") (pinfunction "IO_L14N_1_147") (pintype "bidirectional"))
    )
    (net (code "169") (name "Net-(U1B-IO_L14P_1)") (class "Default")
      (node (ref "RP7") (pin "14") (pintype "passive"))
      (node (ref "U1") (pin "146") (pinfunction "IO_L14P_1_146") (pintype "bidirectional"))
    )
    (net (code "170") (name "Net-(U1B-IO_L15N_1{slash}LDC0)") (class "Default")
      (node (ref "RP7") (pin "11") (pintype "passive"))
      (node (ref "U1") (pin "151") (pinfunction "IO_L15N_1/LDC0_151") (pintype "bidirectional"))
    )
    (net (code "171") (name "Net-(U1B-IO_L15P_1{slash}HDC)") (class "Default")
      (node (ref "RP7") (pin "12") (pintype "passive"))
      (node (ref "U1") (pin "150") (pinfunction "IO_L15P_1/HDC_150") (pintype "bidirectional"))
    )
    (net (code "172") (name "Net-(U1B-IO_L16N_1{slash}LDC2)") (class "Default")
      (node (ref "RP7") (pin "9") (pintype "passive"))
      (node (ref "U1") (pin "153") (pinfunction "IO_L16N_1/LDC2_153") (pintype "bidirectional"))
    )
    (net (code "173") (name "Net-(U1B-IO_L16P_1{slash}LDC1)") (class "Default")
      (node (ref "RP7") (pin "10") (pintype "passive"))
      (node (ref "U1") (pin "152") (pinfunction "IO_L16P_1/LDC1_152") (pintype "bidirectional"))
    )
    (net (code "174") (name "Net-(U1C-IO_L01P_2{slash}CSO_B)") (class "Default")
      (node (ref "RP1") (pin "16") (pintype "passive"))
      (node (ref "U1") (pin "55") (pinfunction "IO_L01P_2/CSO_B_55") (pintype "bidirectional"))
    )
    (net (code "175") (name "Net-(U1C-IO_L03N_2{slash}MOSI{slash}CSI_B)") (class "Default")
      (node (ref "RP1") (pin "14") (pintype "passive"))
      (node (ref "U1") (pin "61") (pinfunction "IO_L03N_2/MOSI/CSI_B_61") (pintype "bidirectional"))
    )
    (net (code "176") (name "Net-(U1C-IO_L03P_2{slash}DOUT{slash}BUSY)") (class "Default")
      (node (ref "RP1") (pin "15") (pintype "passive"))
      (node (ref "U1") (pin "60") (pinfunction "IO_L03P_2/DOUT/BUSY_60") (pintype "bidirectional"))
    )
    (net (code "177") (name "Net-(U1C-IO_L04N_2)") (class "Default")
      (node (ref "RP1") (pin "12") (pintype "passive"))
      (node (ref "U1") (pin "63") (pinfunction "IO_L04N_2_63") (pintype "bidirectional"))
    )
    (net (code "178") (name "Net-(U1C-IO_L04P_2)") (class "Default")
      (node (ref "RP1") (pin "13") (pintype "passive"))
      (node (ref "U1") (pin "62") (pinfunction "IO_L04P_2_62") (pintype "bidirectional"))
    )
    (net (code "179") (name "Net-(U1C-IO_L05N_2)") (class "Default")
      (node (ref "RP1") (pin "10") (pintype "passive"))
      (node (ref "U1") (pin "65") (pinfunction "IO_L05N_2_65") (pintype "bidirectional"))
    )
    (net (code "180") (name "Net-(U1C-IO_L05P_2)") (class "Default")
      (node (ref "RP1") (pin "11") (pintype "passive"))
      (node (ref "U1") (pin "64") (pinfunction "IO_L05P_2_64") (pintype "bidirectional"))
    )
    (net (code "181") (name "Net-(U1C-IO_L06N_2)") (class "Default")
      (node (ref "RP4") (pin "16") (pintype "passive"))
      (node (ref "U1") (pin "69") (pinfunction "IO_L06N_2_69") (pintype "bidirectional"))
    )
    (net (code "182") (name "Net-(U1C-IO_L06P_2)") (class "Default")
      (node (ref "RP1") (pin "9") (pintype "passive"))
      (node (ref "U1") (pin "68") (pinfunction "IO_L06P_2_68") (pintype "bidirectional"))
    )
    (net (code "183") (name "Net-(U1C-IO_L08N_2{slash}D6{slash}GCLK13)") (class "Default")
      (node (ref "RP4") (pin "14") (pintype "passive"))
      (node (ref "U1") (pin "75") (pinfunction "IO_L08N_2/D6/GCLK13_75") (pintype "bidirectional"))
    )
    (net (code "184") (name "Net-(U1C-IO_L08P_2{slash}D7{slash}GCLK12)") (class "Default")
      (node (ref "RP4") (pin "15") (pintype "passive"))
      (node (ref "U1") (pin "74") (pinfunction "IO_L08P_2/D7/GCLK12_74") (pintype "bidirectional"))
    )
    (net (code "185") (name "Net-(U1C-IO_L09N_2{slash}D3{slash}GCLK15)") (class "Default")
      (node (ref "RP4") (pin "11") (pintype "passive"))
      (node (ref "U1") (pin "78") (pinfunction "IO_L09N_2/D3/GCLK15_78") (pintype "bidirectional"))
    )
    (net (code "186") (name "Net-(U1C-IO_L09P_2{slash}D4{slash}GCLK14)") (class "Default")
      (node (ref "RP4") (pin "12") (pintype "passive"))
      (node (ref "U1") (pin "77") (pinfunction "IO_L09P_2/D4/GCLK14_77") (pintype "bidirectional"))
    )
    (net (code "187") (name "Net-(U1C-IO_L11N_2{slash}D1{slash}GCLK3)") (class "Default")
      (node (ref "RP4") (pin "9") (pintype "passive"))
      (node (ref "U1") (pin "83") (pinfunction "IO_L11N_2/D1/GCLK3_83") (pintype "bidirectional"))
    )
    (net (code "188") (name "Net-(U1C-IO_L11P_2{slash}D2{slash}GCLK2)") (class "Default")
      (node (ref "RP4") (pin "10") (pintype "passive"))
      (node (ref "U1") (pin "82") (pinfunction "IO_L11P_2/D2/GCLK2_82") (pintype "bidirectional"))
    )
    (net (code "189") (name "Net-(U1C-IO_L13N_2)") (class "Default")
      (node (ref "RP6") (pin "14") (pintype "passive"))
      (node (ref "U1") (pin "90") (pinfunction "IO_L13N_2_90") (pintype "bidirectional"))
    )
    (net (code "190") (name "Net-(U1C-IO_L13P_2)") (class "Default")
      (node (ref "RP6") (pin "15") (pintype "passive"))
      (node (ref "U1") (pin "89") (pinfunction "IO_L13P_2_89") (pintype "bidirectional"))
    )
    (net (code "191") (name "Net-(U1C-IO_L14N_2{slash}A22)") (class "Default")
      (node (ref "RP6") (pin "12") (pintype "passive"))
      (node (ref "U1") (pin "94") (pinfunction "IO_L14N_2/A22_94") (pintype "bidirectional"))
    )
    (net (code "192") (name "Net-(U1C-IO_L14P_2{slash}A23)") (class "Default")
      (node (ref "RP6") (pin "13") (pintype "passive"))
      (node (ref "U1") (pin "93") (pinfunction "IO_L14P_2/A23_93") (pintype "bidirectional"))
    )
    (net (code "193") (name "Net-(U1C-IO_L15N_2{slash}A20)") (class "Default")
      (node (ref "RP6") (pin "10") (pintype "passive"))
      (node (ref "U1") (pin "97") (pinfunction "IO_L15N_2/A20_97") (pintype "bidirectional"))
    )
    (net (code "194") (name "Net-(U1C-IO_L15P_2{slash}A21)") (class "Default")
      (node (ref "RP6") (pin "11") (pintype "passive"))
      (node (ref "U1") (pin "96") (pinfunction "IO_L15P_2/A21_96") (pintype "bidirectional"))
    )
    (net (code "195") (name "Net-(U1C-IO{slash}D5)") (class "Default")
      (node (ref "RP4") (pin "13") (pintype "passive"))
      (node (ref "U1") (pin "76") (pinfunction "IO/D5_76") (pintype "bidirectional"))
    )
    (net (code "196") (name "Net-(U1C-IO{slash}VREF_2)") (class "Default")
      (node (ref "RP6") (pin "9") (pintype "passive"))
      (node (ref "U1") (pin "98") (pinfunction "IO/VREF_2_98") (pintype "bidirectional"))
    )
    (net (code "197") (name "VCC") (class "Default")
      (node (ref "C60") (pin "1") (pintype "passive"))
      (node (ref "U11") (pin "8") (pinfunction "VCC_8") (pintype "passive"))
    )
    (net (code "198") (name "unconnected-(RP3-Pad5)") (class "Default")
      (node (ref "RP3") (pin "5") (pintype "passive"))
    )
    (net (code "199") (name "unconnected-(RP3-Pad12)") (class "Default")
      (node (ref "RP3") (pin "12") (pintype "passive"))
    )
    (net (code "200") (name "unconnected-(U1A-IO-Pad187)") (class "Default")
      (node (ref "U1") (pin "187") (pinfunction "IO_187") (pintype "bidirectional"))
    )
    (net (code "201") (name "unconnected-(U1A-IO_L01N_0-Pad161)") (class "Default")
      (node (ref "U1") (pin "161") (pinfunction "IO_L01N_0_161") (pintype "bidirectional"))
    )
    (net (code "202") (name "unconnected-(U1A-IO_L01P_0-Pad160)") (class "Default")
      (node (ref "U1") (pin "160") (pinfunction "IO_L01P_0_160") (pintype "bidirectional"))
    )
    (net (code "203") (name "unconnected-(U1A-IO_L02P_0-Pad162)") (class "Default")
      (node (ref "U1") (pin "162") (pinfunction "IO_L02P_0_162") (pintype "bidirectional"))
    )
    (net (code "204") (name "unconnected-(U1A-IO_L03N_0-Pad165)") (class "Default")
      (node (ref "U1") (pin "165") (pinfunction "IO_L03N_0_165") (pintype "bidirectional"))
    )
    (net (code "205") (name "unconnected-(U1A-IO_L10N_0{slash}GCLK11-Pad186)") (class "Default")
      (node (ref "U1") (pin "186") (pinfunction "IO_L10N_0/GCLK11_186") (pintype "bidirectional"))
    )
    (net (code "206") (name "unconnected-(U1A-IO_L10P_0{slash}GCLK10-Pad185)") (class "Default")
      (node (ref "U1") (pin "185") (pinfunction "IO_L10P_0/GCLK10_185") (pintype "bidirectional"))
    )
    (net (code "207") (name "unconnected-(U1A-IO_L15N_0-Pad203)") (class "Default")
      (node (ref "U1") (pin "203") (pinfunction "IO_L15N_0_203") (pintype "bidirectional"))
    )
    (net (code "208") (name "unconnected-(U1A-IO_L15P_0-Pad202)") (class "Default")
      (node (ref "U1") (pin "202") (pinfunction "IO_L15P_0_202") (pintype "bidirectional"))
    )
    (net (code "209") (name "unconnected-(U1A-IO_L16P_0-Pad205)") (class "Default")
      (node (ref "U1") (pin "205") (pinfunction "IO_L16P_0_205") (pintype "bidirectional"))
    )
    (net (code "210") (name "unconnected-(U1B-IO_L07P_1{slash}A10{slash}RHCLK0-Pad126)") (class "Default")
      (node (ref "U1") (pin "126") (pinfunction "IO_L07P_1/A10/RHCLK0_126") (pintype "bidirectional"))
    )
    (net (code "211") (name "unconnected-(U1C-IO_L16N_2{slash}VS1{slash}A18-Pad100)") (class "Default")
      (node (ref "U1") (pin "100") (pinfunction "IO_L16N_2/VS1/A18_100") (pintype "bidirectional"))
    )
    (net (code "212") (name "unconnected-(U1C-IO_L16P_2{slash}VS2{slash}A19-Pad99)") (class "Default")
      (node (ref "U1") (pin "99") (pinfunction "IO_L16P_2/VS2/A19_99") (pintype "bidirectional"))
    )
    (net (code "213") (name "unconnected-(U1C-IO_L17P_2{slash}VS0{slash}A17-Pad102)") (class "Default")
      (node (ref "U1") (pin "102") (pinfunction "IO_L17P_2/VS0/A17_102") (pintype "bidirectional"))
    )
    (net (code "214") (name "unconnected-(U1D-IO_L01P_3-Pad2)") (class "Default")
      (node (ref "U1") (pin "2") (pinfunction "IO_L01P_3_2") (pintype "bidirectional"))
    )
    (net (code "215") (name "unconnected-(U1E-IP-Pad6)") (class "Default")
      (node (ref "U1") (pin "6") (pinfunction "IP_6") (pintype "input"))
    )
    (net (code "216") (name "unconnected-(U1E-IP-Pad14)") (class "Default")
      (node (ref "U1") (pin "14") (pinfunction "IP_14") (pintype "input"))
    )
    (net (code "217") (name "unconnected-(U1E-IP-Pad26)") (class "Default")
      (node (ref "U1") (pin "26") (pinfunction "IP_26") (pintype "input"))
    )
    (net (code "218") (name "unconnected-(U1E-IP-Pad32)") (class "Default")
      (node (ref "U1") (pin "32") (pinfunction "IP_32") (pintype "input"))
    )
    (net (code "219") (name "unconnected-(U1E-IP-Pad43)") (class "Default")
      (node (ref "U1") (pin "43") (pinfunction "IP_43") (pintype "input"))
    )
    (net (code "220") (name "unconnected-(U1E-IP-Pad51)") (class "Default")
      (node (ref "U1") (pin "51") (pinfunction "IP_51") (pintype "input"))
    )
    (net (code "221") (name "unconnected-(U1E-IP-Pad54)") (class "Default")
      (node (ref "U1") (pin "54") (pinfunction "IP_54") (pintype "input"))
    )
    (net (code "222") (name "unconnected-(U1E-IP-Pad91)") (class "Default")
      (node (ref "U1") (pin "91") (pinfunction "IP_91") (pintype "input"))
    )
    (net (code "223") (name "unconnected-(U1E-IP-Pad101)") (class "Default")
      (node (ref "U1") (pin "101") (pinfunction "IP_101") (pintype "input"))
    )
    (net (code "224") (name "unconnected-(U1E-IP-Pad110)") (class "Default")
      (node (ref "U1") (pin "110") (pinfunction "IP_110") (pintype "input"))
    )
    (net (code "225") (name "unconnected-(U1E-IP-Pad118)") (class "Default")
      (node (ref "U1") (pin "118") (pinfunction "IP_118") (pintype "input"))
    )
    (net (code "226") (name "unconnected-(U1E-IP-Pad124)") (class "Default")
      (node (ref "U1") (pin "124") (pinfunction "IP_124") (pintype "input"))
    )
    (net (code "227") (name "unconnected-(U1E-IP-Pad130)") (class "Default")
      (node (ref "U1") (pin "130") (pinfunction "IP_130") (pintype "input"))
    )
    (net (code "228") (name "unconnected-(U1E-IP-Pad142)") (class "Default")
      (node (ref "U1") (pin "142") (pinfunction "IP_142") (pintype "input"))
    )
    (net (code "229") (name "unconnected-(U1E-IP-Pad148)") (class "Default")
      (node (ref "U1") (pin "148") (pinfunction "IP_148") (pintype "input"))
    )
    (net (code "230") (name "unconnected-(U1E-IP-Pad154)") (class "Default")
      (node (ref "U1") (pin "154") (pinfunction "IP_154") (pintype "input"))
    )
    (net (code "231") (name "unconnected-(U1E-IP-Pad159)") (class "Default")
      (node (ref "U1") (pin "159") (pinfunction "IP_159") (pintype "input"))
    )
    (net (code "232") (name "unconnected-(U1E-IP-Pad169)") (class "Default")
      (node (ref "U1") (pin "169") (pinfunction "IP_169") (pintype "input"))
    )
    (net (code "233") (name "unconnected-(U1E-IP-Pad194)") (class "Default")
      (node (ref "U1") (pin "194") (pinfunction "IP_194") (pintype "input"))
    )
    (net (code "234") (name "unconnected-(U1E-IP-Pad204)") (class "Default")
      (node (ref "U1") (pin "204") (pinfunction "IP_204") (pintype "input"))
    )
    (net (code "235") (name "unconnected-(U1E-IP_L02N_2-Pad58)") (class "Default")
      (node (ref "U1") (pin "58") (pinfunction "IP_L02N_2_58") (pintype "input"))
    )
    (net (code "236") (name "unconnected-(U1E-IP_L02P_2-Pad57)") (class "Default")
      (node (ref "U1") (pin "57") (pinfunction "IP_L02P_2_57") (pintype "input"))
    )
    (net (code "237") (name "unconnected-(U1E-IP_L06N_0-Pad175)") (class "Default")
      (node (ref "U1") (pin "175") (pinfunction "IP_L06N_0_175") (pintype "input"))
    )
    (net (code "238") (name "unconnected-(U1E-IP_L06P_0-Pad174)") (class "Default")
      (node (ref "U1") (pin "174") (pinfunction "IP_L06P_0_174") (pintype "input"))
    )
    (net (code "239") (name "unconnected-(U1E-IP_L07N_2{slash}VREF_2-Pad72)") (class "Default")
      (node (ref "U1") (pin "72") (pinfunction "IP_L07N_2/VREF_2_72") (pintype "input"))
    )
    (net (code "240") (name "unconnected-(U1E-IP_L07P_2-Pad71)") (class "Default")
      (node (ref "U1") (pin "71") (pinfunction "IP_L07P_2_71") (pintype "input"))
    )
    (net (code "241") (name "unconnected-(U1E-IP_L09N_0{slash}GCLK9-Pad184)") (class "Default")
      (node (ref "U1") (pin "184") (pinfunction "IP_L09N_0/GCLK9_184") (pintype "input"))
    )
    (net (code "242") (name "unconnected-(U1E-IP_L09P_0{slash}GCLK8-Pad183)") (class "Default")
      (node (ref "U1") (pin "183") (pinfunction "IP_L09P_0/GCLK8_183") (pintype "input"))
    )
    (net (code "243") (name "unconnected-(U1E-IP{slash}VREF_1-Pad136)") (class "Default")
      (node (ref "U1") (pin "136") (pinfunction "IP/VREF_1_136") (pintype "input"))
    )
    (net (code "244") (name "unconnected-(U1E-IP{slash}VREF_3-Pad20)") (class "Default")
      (node (ref "U1") (pin "20") (pinfunction "IP/VREF_3_20") (pintype "input"))
    )
  )
)
